# UI.net
KiCad netlist of a schematic drawn in EAGLE
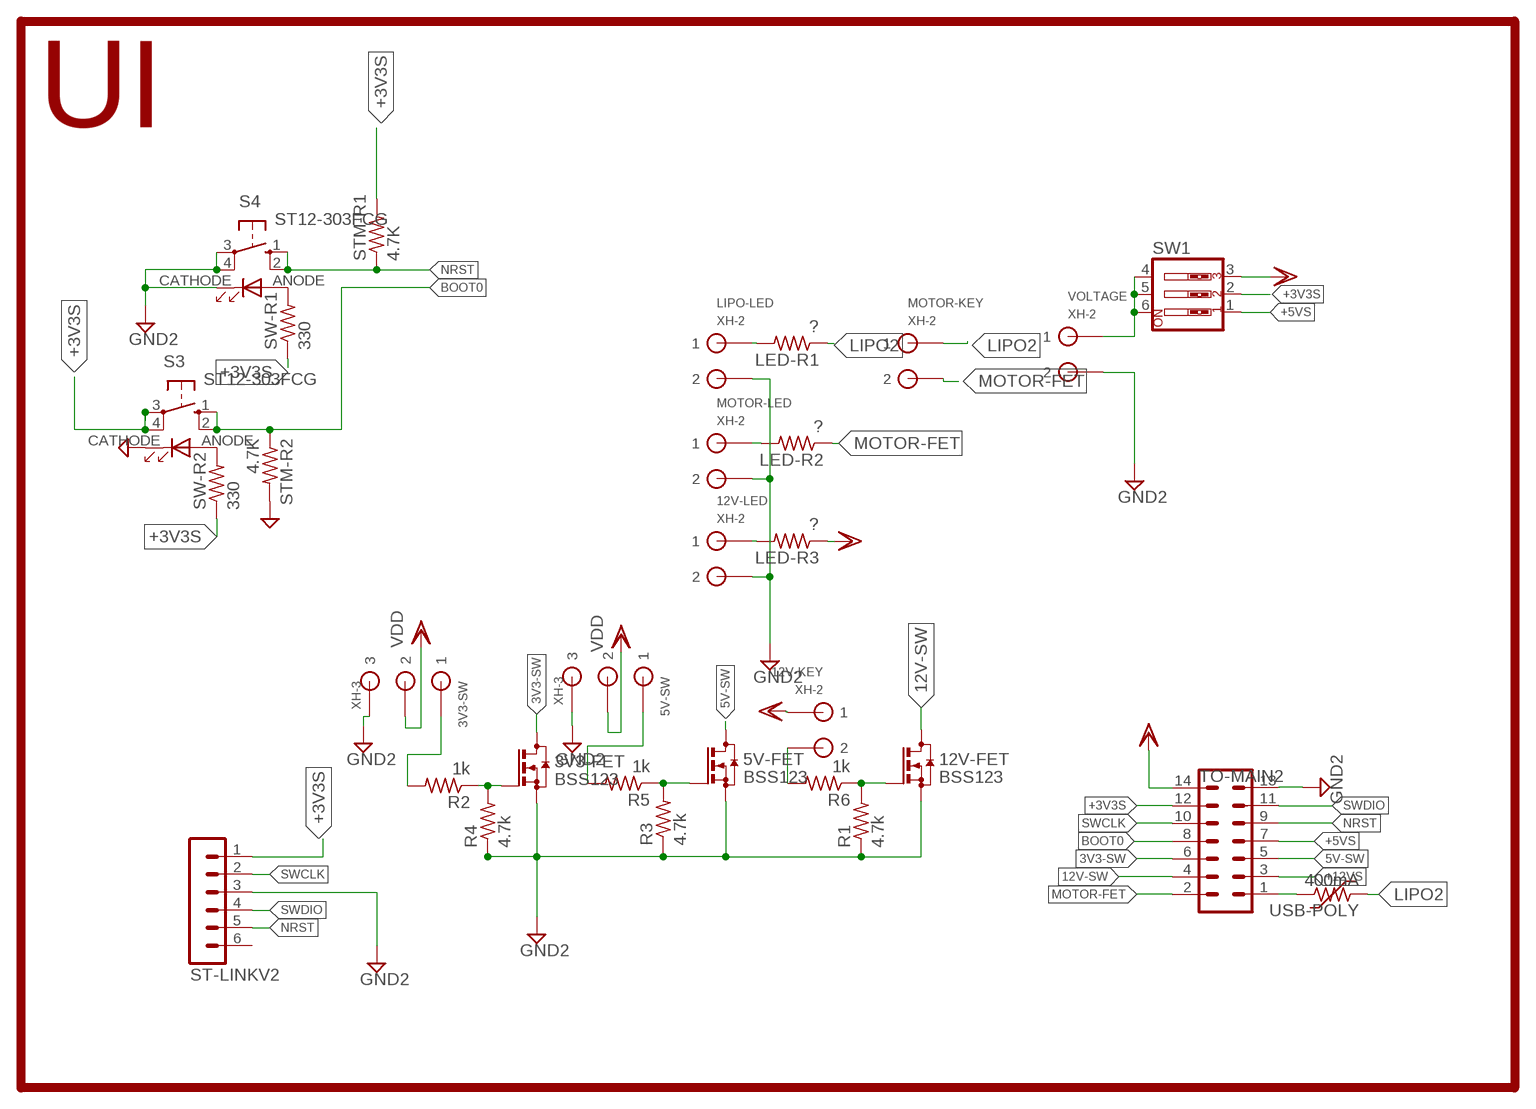
[diagram p0: schematic, sheet 1]

(export (version "E")
  (design (tool "Eeschema 10.0.6"))
  (components
    (comp (ref "3V3-FET")
      (value "BSS123")
      (footprint "eagle-import:SOT23")
      (libsource (lib "eagle-import") (part "BSS123"))
    )
    (comp (ref "3V3-SW")
      (value "XH-3")
      (footprint "eagle-import:CON3")
      (libsource (lib "eagle-import") (part "XH-3"))
    )
    (comp (ref "5V-FET")
      (value "BSS123")
      (footprint "eagle-import:SOT23")
      (libsource (lib "eagle-import") (part "BSS123"))
    )
    (comp (ref "5V-SW")
      (value "XH-3")
      (footprint "eagle-import:CON3")
      (libsource (lib "eagle-import") (part "XH-3"))
    )
    (comp (ref "12V-FET")
      (value "BSS123")
      (footprint "eagle-import:SOT23")
      (libsource (lib "eagle-import") (part "BSS123"))
    )
    (comp (ref "12V-KEY")
      (value "XH-2")
      (footprint "eagle-import:CON2")
      (libsource (lib "eagle-import") (part "XH-2"))
    )
    (comp (ref "12V-LED")
      (value "XH-2")
      (footprint "eagle-import:CON2")
      (libsource (lib "eagle-import") (part "XH-2"))
    )
    (comp (ref "LED-R1")
      (value "?")
      (footprint "eagle-import:M0805")
      (libsource (lib "eagle-import") (part "resistor_348_R-US_M0805"))
    )
    (comp (ref "LED-R2")
      (value "?")
      (footprint "eagle-import:M0805")
      (libsource (lib "eagle-import") (part "resistor_348_R-US_M0805"))
    )
    (comp (ref "LED-R3")
      (value "?")
      (footprint "eagle-import:M0805")
      (libsource (lib "eagle-import") (part "resistor_348_R-US_M0805"))
    )
    (comp (ref "LIPO-LED")
      (value "XH-2")
      (footprint "eagle-import:CON2")
      (libsource (lib "eagle-import") (part "XH-2"))
    )
    (comp (ref "MOTOR-KEY")
      (value "XH-2")
      (footprint "eagle-import:CON2")
      (libsource (lib "eagle-import") (part "XH-2"))
    )
    (comp (ref "MOTOR-LED")
      (value "XH-2")
      (footprint "eagle-import:CON2")
      (libsource (lib "eagle-import") (part "XH-2"))
    )
    (comp (ref "R1")
      (value "4.7k")
      (footprint "eagle-import:M0805")
      (libsource (lib "eagle-import") (part "resistor_348_R-US_M0805"))
    )
    (comp (ref "R2")
      (value "1k")
      (footprint "eagle-import:M0805")
      (libsource (lib "eagle-import") (part "resistor_348_R-US_M0805"))
    )
    (comp (ref "R3")
      (value "4.7k")
      (footprint "eagle-import:M0805")
      (libsource (lib "eagle-import") (part "resistor_348_R-US_M0805"))
    )
    (comp (ref "R4")
      (value "4.7k")
      (footprint "eagle-import:M0805")
      (libsource (lib "eagle-import") (part "resistor_348_R-US_M0805"))
    )
    (comp (ref "R5")
      (value "1k")
      (footprint "eagle-import:M0805")
      (libsource (lib "eagle-import") (part "resistor_348_R-US_M0805"))
    )
    (comp (ref "R6")
      (value "1k")
      (footprint "eagle-import:M0805")
      (libsource (lib "eagle-import") (part "resistor_348_R-US_M0805"))
    )
    (comp (ref "S3")
      (value "ST12-303FCG")
      (footprint "eagle-import:ST12303FCG")
      (libsource (lib "eagle-import") (part "ST12-303FCG"))
    )
    (comp (ref "S4")
      (value "ST12-303FCG")
      (footprint "eagle-import:ST12303FCG")
      (libsource (lib "eagle-import") (part "ST12-303FCG"))
    )
    (comp (ref "ST-LINKV2")
      (value "MA06-1")
      (footprint "eagle-import:MA06-1")
      (libsource (lib "eagle-import") (part "MA06-1"))
    )
    (comp (ref "STM-R1")
      (value "4.7K")
      (footprint "eagle-import:R0805")
      (libsource (lib "eagle-import") (part "R-US_R0805"))
    )
    (comp (ref "STM-R2")
      (value "4.7K")
      (footprint "eagle-import:R0805")
      (libsource (lib "eagle-import") (part "R-US_R0805"))
    )
    (comp (ref "SW-R1")
      (value "330")
      (footprint "eagle-import:R0805")
      (libsource (lib "eagle-import") (part "R-US_R0805"))
    )
    (comp (ref "SW-R2")
      (value "330")
      (footprint "eagle-import:R0805")
      (libsource (lib "eagle-import") (part "R-US_R0805"))
    )
    (comp (ref "SW1")
      (value "SW_DIP-3")
      (footprint "eagle-import:EDG-03")
      (libsource (lib "eagle-import") (part "SW_DIP-3"))
    )
    (comp (ref "TO-MAIN2")
      (value "ML14")
      (footprint "eagle-import:ML14")
      (libsource (lib "eagle-import") (part "ML14"))
    )
    (comp (ref "USB-POLY")
      (value "400mA")
      (footprint "eagle-import:MF-5_1")
      (libsource (lib "eagle-import") (part "PTC-MF-5,1"))
    )
    (comp (ref "VOLTAGE")
      (value "XH-2")
      (footprint "eagle-import:CON2")
      (libsource (lib "eagle-import") (part "XH-2"))
    )
  )
  (nets
    (net (code "1") (name "+3V3S") (class "Default")
      (node (ref "S3") (pin "3") (pinfunction "3_3") (pintype "passive"))
      (node (ref "S3") (pin "4") (pinfunction "4_4") (pintype "passive"))
      (node (ref "ST-LINKV2") (pin "1") (pinfunction "1_1") (pintype "passive"))
      (node (ref "STM-R1") (pin "2") (pinfunction "2_2") (pintype "passive"))
      (node (ref "SW-R1") (pin "1") (pinfunction "1_1") (pintype "passive"))
      (node (ref "SW-R2") (pin "1") (pinfunction "1_1") (pintype "passive"))
      (node (ref "SW1") (pin "2") (pinfunction "2_2") (pintype "passive"))
      (node (ref "TO-MAIN2") (pin "12") (pinfunction "12_12") (pintype "passive"))
    )
    (net (code "2") (name "+5VS") (class "Default")
      (node (ref "SW1") (pin "1") (pinfunction "1_1") (pintype "passive"))
      (node (ref "TO-MAIN2") (pin "7") (pinfunction "7_7") (pintype "passive"))
    )
    (net (code "3") (name "+12VS") (class "Default")
      (node (ref "TO-MAIN2") (pin "3") (pinfunction "3_3") (pintype "passive"))
    )
    (net (code "4") (name "3V3-SW") (class "Default")
      (node (ref "3V3-FET") (pin "3") (pinfunction "D_3") (pintype "passive"))
      (node (ref "TO-MAIN2") (pin "6") (pinfunction "6_6") (pintype "passive"))
    )
    (net (code "5") (name "5V-SW") (class "Default")
      (node (ref "5V-FET") (pin "3") (pinfunction "D_3") (pintype "passive"))
      (node (ref "TO-MAIN2") (pin "5") (pinfunction "5_5") (pintype "passive"))
    )
    (net (code "6") (name "12V-SW") (class "Default")
      (node (ref "12V-FET") (pin "3") (pinfunction "D_3") (pintype "passive"))
      (node (ref "TO-MAIN2") (pin "4") (pinfunction "4_4") (pintype "passive"))
    )
    (net (code "7") (name "BOOT0") (class "Default")
      (node (ref "S3") (pin "1") (pinfunction "1_1") (pintype "passive"))
      (node (ref "S3") (pin "2") (pinfunction "2_2") (pintype "passive"))
      (node (ref "STM-R2") (pin "1") (pinfunction "1_1") (pintype "passive"))
      (node (ref "TO-MAIN2") (pin "8") (pinfunction "8_8") (pintype "passive"))
    )
    (net (code "8") (name "GND2") (class "Default")
      (node (ref "12V-FET") (pin "2") (pinfunction "S_2") (pintype "passive"))
      (node (ref "12V-LED") (pin "P$2") (pinfunction "2_P$2") (pintype "bidirectional"))
      (node (ref "3V3-FET") (pin "2") (pinfunction "S_2") (pintype "passive"))
      (node (ref "3V3-SW") (pin "P$3") (pinfunction "3_P$3") (pintype "bidirectional"))
      (node (ref "5V-FET") (pin "2") (pinfunction "S_2") (pintype "passive"))
      (node (ref "5V-SW") (pin "P$3") (pinfunction "3_P$3") (pintype "bidirectional"))
      (node (ref "LIPO-LED") (pin "P$2") (pinfunction "2_P$2") (pintype "bidirectional"))
      (node (ref "MOTOR-LED") (pin "P$2") (pinfunction "2_P$2") (pintype "bidirectional"))
      (node (ref "R1") (pin "1") (pinfunction "1_1") (pintype "passive"))
      (node (ref "R3") (pin "1") (pinfunction "1_1") (pintype "passive"))
      (node (ref "R4") (pin "1") (pinfunction "1_1") (pintype "passive"))
      (node (ref "S3") (pin "CATHODE") (pinfunction "C_CATHODE") (pintype "passive"))
      (node (ref "S4") (pin "3") (pinfunction "3_3") (pintype "passive"))
      (node (ref "S4") (pin "4") (pinfunction "4_4") (pintype "passive"))
      (node (ref "S4") (pin "CATHODE") (pinfunction "C_CATHODE") (pintype "passive"))
      (node (ref "ST-LINKV2") (pin "3") (pinfunction "3_3") (pintype "passive"))
      (node (ref "STM-R2") (pin "2") (pinfunction "2_2") (pintype "passive"))
      (node (ref "TO-MAIN2") (pin "13") (pinfunction "13_13") (pintype "passive"))
      (node (ref "VOLTAGE") (pin "P$2") (pinfunction "2_P$2") (pintype "bidirectional"))
    )
    (net (code "9") (name "LIPO2") (class "Default")
      (node (ref "LED-R1") (pin "1") (pinfunction "1_1") (pintype "passive"))
      (node (ref "MOTOR-KEY") (pin "P$1") (pinfunction "1_P$1") (pintype "bidirectional"))
      (node (ref "USB-POLY") (pin "1") (pinfunction "1_1") (pintype "passive"))
    )
    (net (code "10") (name "MOTOR-FET") (class "Default")
      (node (ref "LED-R2") (pin "1") (pinfunction "1_1") (pintype "passive"))
      (node (ref "MOTOR-KEY") (pin "P$2") (pinfunction "2_P$2") (pintype "bidirectional"))
      (node (ref "TO-MAIN2") (pin "2") (pinfunction "2_2") (pintype "passive"))
    )
    (net (code "11") (name "NRST") (class "Default")
      (node (ref "S4") (pin "1") (pinfunction "1_1") (pintype "passive"))
      (node (ref "S4") (pin "2") (pinfunction "2_2") (pintype "passive"))
      (node (ref "ST-LINKV2") (pin "5") (pinfunction "5_5") (pintype "passive"))
      (node (ref "STM-R1") (pin "1") (pinfunction "1_1") (pintype "passive"))
      (node (ref "TO-MAIN2") (pin "9") (pinfunction "9_9") (pintype "passive"))
    )
    (net (code "12") (name "Net-(3V3-FET-G)") (class "Default")
      (node (ref "3V3-FET") (pin "1") (pinfunction "G_1") (pintype "passive"))
      (node (ref "R2") (pin "1") (pinfunction "1_1") (pintype "passive"))
      (node (ref "R4") (pin "2") (pinfunction "2_2") (pintype "passive"))
    )
    (net (code "13") (name "Net-(3V3-SW-1)") (class "Default")
      (node (ref "3V3-SW") (pin "P$1") (pinfunction "1_P$1") (pintype "bidirectional"))
      (node (ref "R2") (pin "2") (pinfunction "2_2") (pintype "passive"))
    )
    (net (code "14") (name "Net-(5V-FET-G)") (class "Default")
      (node (ref "5V-FET") (pin "1") (pinfunction "G_1") (pintype "passive"))
      (node (ref "R3") (pin "2") (pinfunction "2_2") (pintype "passive"))
      (node (ref "R5") (pin "1") (pinfunction "1_1") (pintype "passive"))
    )
    (net (code "15") (name "Net-(5V-SW-1)") (class "Default")
      (node (ref "5V-SW") (pin "P$1") (pinfunction "1_P$1") (pintype "bidirectional"))
      (node (ref "R5") (pin "2") (pinfunction "2_2") (pintype "passive"))
    )
    (net (code "16") (name "Net-(12V-FET-G)") (class "Default")
      (node (ref "12V-FET") (pin "1") (pinfunction "G_1") (pintype "passive"))
      (node (ref "R1") (pin "2") (pinfunction "2_2") (pintype "passive"))
      (node (ref "R6") (pin "1") (pinfunction "1_1") (pintype "passive"))
    )
    (net (code "17") (name "Net-(12V-KEY-2)") (class "Default")
      (node (ref "12V-KEY") (pin "P$2") (pinfunction "2_P$2") (pintype "bidirectional"))
      (node (ref "R6") (pin "2") (pinfunction "2_2") (pintype "passive"))
    )
    (net (code "18") (name "Net-(12V-LED-1)") (class "Default")
      (node (ref "12V-LED") (pin "P$1") (pinfunction "1_P$1") (pintype "bidirectional"))
      (node (ref "LED-R3") (pin "2") (pinfunction "2_2") (pintype "passive"))
    )
    (net (code "19") (name "Net-(LIPO-LED-1)") (class "Default")
      (node (ref "LED-R1") (pin "2") (pinfunction "2_2") (pintype "passive"))
      (node (ref "LIPO-LED") (pin "P$1") (pinfunction "1_P$1") (pintype "bidirectional"))
    )
    (net (code "20") (name "Net-(MOTOR-LED-1)") (class "Default")
      (node (ref "LED-R2") (pin "2") (pinfunction "2_2") (pintype "passive"))
      (node (ref "MOTOR-LED") (pin "P$1") (pinfunction "1_P$1") (pintype "bidirectional"))
    )
    (net (code "21") (name "Net-(S3-A)") (class "Default")
      (node (ref "S3") (pin "ANODE") (pinfunction "A_ANODE") (pintype "passive"))
      (node (ref "SW-R2") (pin "2") (pinfunction "2_2") (pintype "passive"))
    )
    (net (code "22") (name "Net-(S4-A)") (class "Default")
      (node (ref "S4") (pin "ANODE") (pinfunction "A_ANODE") (pintype "passive"))
      (node (ref "SW-R1") (pin "2") (pinfunction "2_2") (pintype "passive"))
    )
    (net (code "23") (name "Net-(TO-MAIN2-Pad1)") (class "Default")
      (node (ref "TO-MAIN2") (pin "1") (pinfunction "1_1") (pintype "passive"))
      (node (ref "USB-POLY") (pin "2") (pinfunction "2_2") (pintype "passive"))
    )
    (net (code "24") (name "Net-(VOLTAGE-1)") (class "Default")
      (node (ref "SW1") (pin "4") (pinfunction "4_4") (pintype "passive"))
      (node (ref "SW1") (pin "5") (pinfunction "5_5") (pintype "passive"))
      (node (ref "SW1") (pin "6") (pinfunction "6_6") (pintype "passive"))
      (node (ref "VOLTAGE") (pin "P$1") (pinfunction "1_P$1") (pintype "bidirectional"))
    )
    (net (code "25") (name "SWCLK") (class "Default")
      (node (ref "ST-LINKV2") (pin "2") (pinfunction "2_2") (pintype "passive"))
      (node (ref "TO-MAIN2") (pin "10") (pinfunction "10_10") (pintype "passive"))
    )
    (net (code "26") (name "SWDIO") (class "Default")
      (node (ref "ST-LINKV2") (pin "4") (pinfunction "4_4") (pintype "passive"))
      (node (ref "TO-MAIN2") (pin "11") (pinfunction "11_11") (pintype "passive"))
    )
    (net (code "27") (name "VDD") (class "Default")
      (node (ref "12V-KEY") (pin "P$1") (pinfunction "1_P$1") (pintype "bidirectional"))
      (node (ref "3V3-SW") (pin "P$2") (pinfunction "2_P$2") (pintype "bidirectional"))
      (node (ref "5V-SW") (pin "P$2") (pinfunction "2_P$2") (pintype "bidirectional"))
      (node (ref "LED-R3") (pin "1") (pinfunction "1_1") (pintype "passive"))
      (node (ref "SW1") (pin "3") (pinfunction "3_3") (pintype "passive"))
      (node (ref "TO-MAIN2") (pin "14") (pinfunction "14_14") (pintype "passive"))
    )
    (net (code "28") (name "unconnected-(ST-LINKV2-Pad6)") (class "Default")
      (node (ref "ST-LINKV2") (pin "6") (pinfunction "6_6") (pintype "passive"))
    )
  )
)
